# nRF52832.net
KiCad netlist of a schematic drawn in Altium Designer
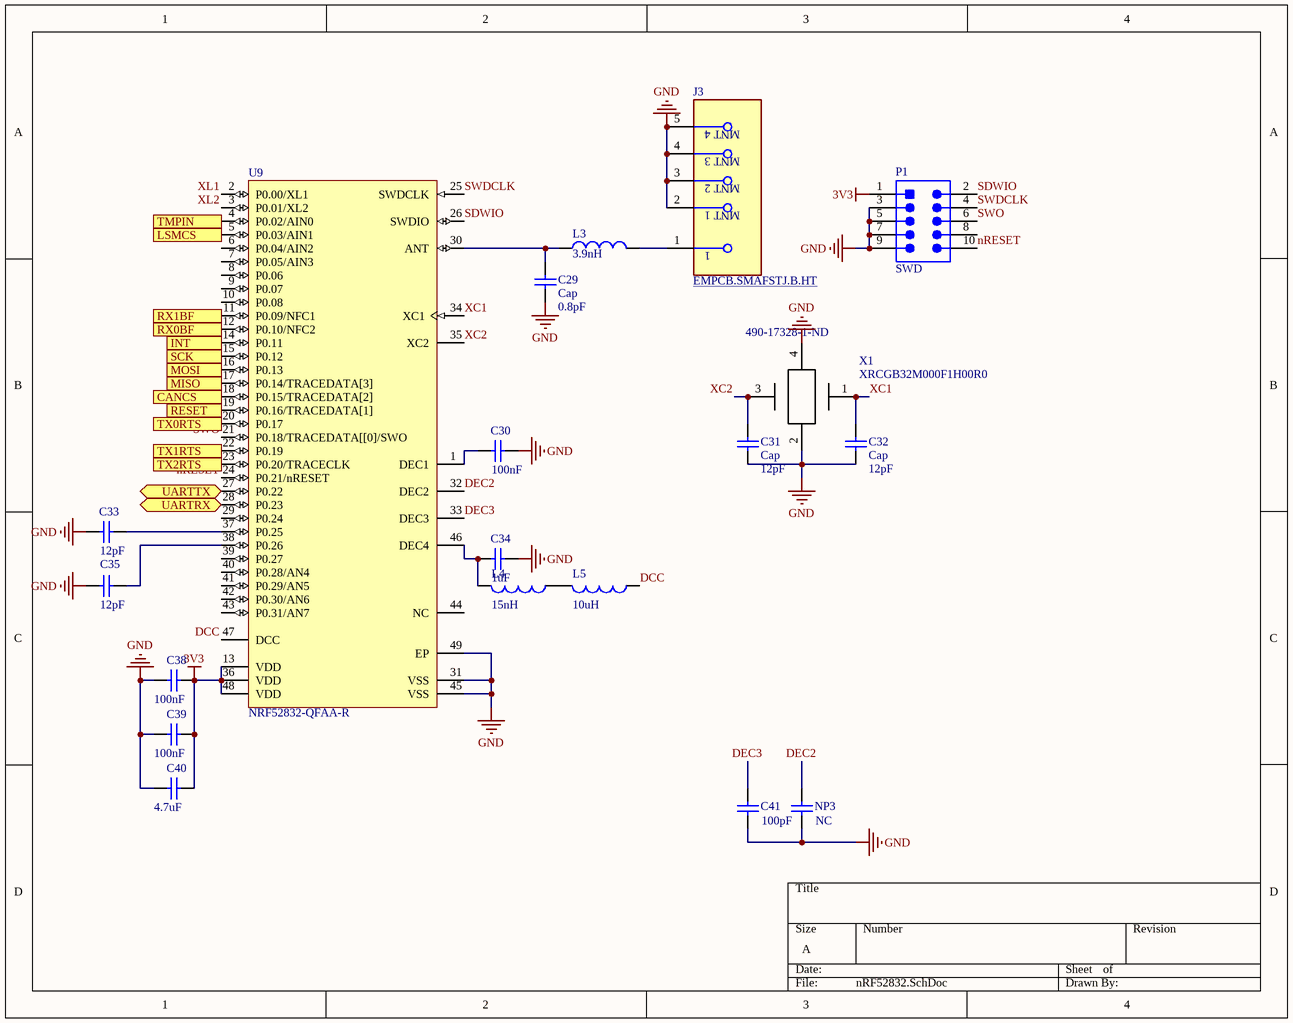
[diagram p0: nRF52832.SchDoc]

(export (version "E")
  (design (tool "Eeschema 10.0.6"))
  (components
    (comp (ref "C29")
      (value "Cap")
      (footprint "0402-A")
      (description "Capacitor")
      (fields (field (name "ALTIUM_VALUE") "0.8pF") (field (name "PUBLISHER") "Altium Limited"))
      (libsource (lib "Miscellaneous Devices") (part "Cap"))
    )
    (comp (ref "C30")
      (value "100nF")
      (footprint "0402-A")
      (description "Capacitor")
      (fields (field (name "Comment") "Cap") (field (name "PUBLISHER") "Altium Limited"))
      (libsource (lib "Miscellaneous Devices") (part "Cap"))
    )
    (comp (ref "C31")
      (value "Cap")
      (footprint "0402-A")
      (description "Capacitor")
      (fields (field (name "ALTIUM_VALUE") "12pF") (field (name "PUBLISHER") "Altium Limited"))
      (libsource (lib "Miscellaneous Devices") (part "Cap"))
    )
    (comp (ref "C32")
      (value "Cap")
      (footprint "0402-A")
      (description "Capacitor")
      (fields (field (name "ALTIUM_VALUE") "12pF") (field (name "PUBLISHER") "Altium Limited"))
      (libsource (lib "Miscellaneous Devices") (part "Cap"))
    )
    (comp (ref "C33")
      (value "12pF")
      (footprint "0402-A")
      (description "Capacitor")
      (fields (field (name "Comment") "Cap") (field (name "PUBLISHER") "Altium Limited"))
      (libsource (lib "Miscellaneous Devices") (part "Cap"))
    )
    (comp (ref "C34")
      (value "1uF")
      (footprint "1608[0603]")
      (description "Capacitor")
      (fields (field (name "Comment") "Cap") (field (name "PUBLISHER") "Altium Limited"))
      (libsource (lib "Miscellaneous Devices") (part "Cap"))
    )
    (comp (ref "C35")
      (value "12pF")
      (footprint "0402-A")
      (description "Capacitor")
      (fields (field (name "Comment") "Cap") (field (name "PUBLISHER") "Altium Limited"))
      (libsource (lib "Miscellaneous Devices") (part "Cap"))
    )
    (comp (ref "C38")
      (value "100nF")
      (footprint "0402-A")
      (description "Capacitor")
      (fields (field (name "Comment") "Cap") (field (name "PUBLISHER") "Altium Limited"))
      (libsource (lib "Miscellaneous Devices") (part "Cap"))
    )
    (comp (ref "C39")
      (value "100nF")
      (footprint "0402-A")
      (description "Capacitor")
      (fields (field (name "Comment") "Cap") (field (name "PUBLISHER") "Altium Limited"))
      (libsource (lib "Miscellaneous Devices") (part "Cap"))
    )
    (comp (ref "C40")
      (value "4.7uF")
      (footprint "6-0805_M")
      (description "Capacitor")
      (fields (field (name "Comment") "Cap") (field (name "PUBLISHER") "Altium Limited"))
      (libsource (lib "Miscellaneous Devices") (part "Cap"))
    )
    (comp (ref "C41")
      (value "100pF")
      (footprint "0402-A")
      (description "Capacitor")
      (fields (field (name "Comment") "Cap") (field (name "PUBLISHER") "Altium Limited"))
      (libsource (lib "Miscellaneous Devices") (part "Cap"))
    )
    (comp (ref "J3")
      (value "EMPCB.SMAFSTJ.B.HT")
      (footprint "FP-EMPCB_SMAFSTJ_B_HT-MFG")
      (description "CONN SMA JACK STR 50OHM EDGE MNT")
      (fields
        (field (name "OCTOPART") "https://octopart.com/empcb.smafstj.b.ht-taoglas-24204431")
        (field (name "MANUFACTURER") "Taoglas Limited")
      )
      (libsource (lib "Altium Content Vault") (part "c65b8a639cdaef1819ea20b5466f8fa"))
    )
    (comp (ref "L3")
      (value "3.9nH")
      (footprint "0402-A")
      (description "Inductor")
      (fields (field (name "PUBLISHER") "Altium Limited"))
      (libsource (lib "Miscellaneous Devices") (part "Inductor"))
    )
    (comp (ref "L4")
      (value "15nH")
      (footprint "0402-A")
      (description "Inductor")
      (fields (field (name "PUBLISHER") "Altium Limited"))
      (libsource (lib "Miscellaneous Devices") (part "Inductor"))
    )
    (comp (ref "L5")
      (value "10uH")
      (footprint "1608[0603]")
      (description "Inductor")
      (fields (field (name "PUBLISHER") "Altium Limited"))
      (libsource (lib "Miscellaneous Devices") (part "Inductor"))
    )
    (comp (ref "NP3")
      (value "NC")
      (footprint "0402-A")
      (description "Capacitor")
      (fields (field (name "Comment") "Cap") (field (name "PUBLISHER") "Altium Limited"))
      (libsource (lib "Miscellaneous Devices") (part "Cap"))
    )
    (comp (ref "P1")
      (value "SWD")
      (footprint "SMTC-FTSH-105-01-L-DV-K_V")
      (description "Male Header, Pitch 1.27 mm, 2 x 5 Position, Height 6.25 mm")
      (fields (field (name "MANUFACTURER") "Samtec"))
      (libsource (lib "Altium Content Vault") (part "CN-2P-M-R10"))
    )
    (comp (ref "U9")
      (value "NRF52832-QFAA-R")
      (footprint "NRSC-QF-48_M")
      (fields (field (name "MANUFACTURER") "Nordic Semiconductor"))
      (libsource (lib "Altium Content Vault") (part "NRSC-NRF52832-QF-48"))
    )
    (comp (ref "X1")
      (value "XRCGB32M000F1H00R0")
      (footprint "XRCGB32M000F1H00R0")
      (description "32MHz Crystal Oscillator")
      (fields (field (name "SUPPLIER PART NUMBER 1") "490-17328-1-ND"))
      (libsource (lib "XRCGB32M000F1H00R0") (part "XRCGB32M000F1H00R0"))
    )
  )
  (nets
    (net (code "1") (name "/CANCS") (class "Default")
      (node (ref "U9") (pin "18") (pinfunction "P0.15/TRACEDATA[2]_18") (pintype "bidirectional"))
    )
    (net (code "2") (name "/DCC") (class "Default")
      (node (ref "L5") (pin "1") (pinfunction "1_1") (pintype "passive"))
      (node (ref "U9") (pin "47") (pinfunction "DCC_47") (pintype "power_in"))
    )
    (net (code "3") (name "/DEC2") (class "Default")
      (node (ref "NP3") (pin "2") (pinfunction "2_2") (pintype "passive"))
      (node (ref "U9") (pin "32") (pinfunction "DEC2_32") (pintype "passive"))
    )
    (net (code "4") (name "/DEC3") (class "Default")
      (node (ref "C41") (pin "2") (pinfunction "2_2") (pintype "passive"))
      (node (ref "U9") (pin "33") (pinfunction "DEC3_33") (pintype "passive"))
    )
    (net (code "5") (name "/INT") (class "Default")
      (node (ref "U9") (pin "14") (pinfunction "P0.11_14") (pintype "bidirectional"))
    )
    (net (code "6") (name "/LSMCS") (class "Default")
      (node (ref "U9") (pin "5") (pinfunction "P0.03/AIN1_5") (pintype "bidirectional"))
    )
    (net (code "7") (name "/MISO") (class "Default")
      (node (ref "U9") (pin "17") (pinfunction "P0.14/TRACEDATA[3]_17") (pintype "bidirectional"))
    )
    (net (code "8") (name "/MOSI") (class "Default")
      (node (ref "U9") (pin "16") (pinfunction "P0.13_16") (pintype "bidirectional"))
    )
    (net (code "9") (name "/RESET") (class "Default")
      (node (ref "U9") (pin "19") (pinfunction "P0.16/TRACEDATA[1]_19") (pintype "bidirectional"))
    )
    (net (code "10") (name "/RX0BF") (class "Default")
      (node (ref "U9") (pin "12") (pinfunction "P0.10/NFC2_12") (pintype "bidirectional"))
    )
    (net (code "11") (name "/RX1BF") (class "Default")
      (node (ref "U9") (pin "11") (pinfunction "P0.09/NFC1_11") (pintype "bidirectional"))
    )
    (net (code "12") (name "/SCK") (class "Default")
      (node (ref "U9") (pin "15") (pinfunction "P0.12_15") (pintype "bidirectional"))
    )
    (net (code "13") (name "/SDWIO") (class "Default")
      (node (ref "P1") (pin "2") (pinfunction "2_2") (pintype "passive"))
      (node (ref "U9") (pin "26") (pinfunction "SWDIO_26") (pintype "bidirectional"))
    )
    (net (code "14") (name "/SWDCLK") (class "Default")
      (node (ref "P1") (pin "4") (pinfunction "4_4") (pintype "passive"))
      (node (ref "U9") (pin "25") (pinfunction "SWDCLK_25") (pintype "input"))
    )
    (net (code "15") (name "/SWO") (class "Default")
      (node (ref "P1") (pin "6") (pinfunction "6_6") (pintype "passive"))
      (node (ref "U9") (pin "21") (pinfunction "P0.18/TRACEDATA[[0]/SWO_21") (pintype "bidirectional"))
    )
    (net (code "16") (name "/TMPIN") (class "Default")
      (node (ref "U9") (pin "4") (pinfunction "P0.02/AIN0_4") (pintype "bidirectional"))
    )
    (net (code "17") (name "/TX0RTS") (class "Default")
      (node (ref "U9") (pin "20") (pinfunction "P0.17_20") (pintype "bidirectional"))
    )
    (net (code "18") (name "/TX1RTS") (class "Default")
      (node (ref "U9") (pin "22") (pinfunction "P0.19_22") (pintype "bidirectional"))
    )
    (net (code "19") (name "/TX2RTS") (class "Default")
      (node (ref "U9") (pin "23") (pinfunction "P0.20/TRACECLK_23") (pintype "bidirectional"))
    )
    (net (code "20") (name "/UARTRX") (class "Default")
      (node (ref "U9") (pin "28") (pinfunction "P0.23_28") (pintype "bidirectional"))
    )
    (net (code "21") (name "/UARTTX") (class "Default")
      (node (ref "U9") (pin "27") (pinfunction "P0.22_27") (pintype "bidirectional"))
    )
    (net (code "22") (name "/XC1") (class "Default")
      (node (ref "C32") (pin "2") (pinfunction "2_2") (pintype "passive"))
      (node (ref "U9") (pin "34") (pinfunction "XC1_34") (pintype "input"))
      (node (ref "X1") (pin "1") (pinfunction "1_1") (pintype "passive"))
    )
    (net (code "23") (name "/XC2") (class "Default")
      (node (ref "C31") (pin "2") (pinfunction "2_2") (pintype "passive"))
      (node (ref "U9") (pin "35") (pinfunction "XC2_35") (pintype "passive"))
      (node (ref "X1") (pin "3") (pintype "passive"))
    )
    (net (code "24") (name "/XL1") (class "Default")
      (node (ref "U9") (pin "2") (pinfunction "P0.00/XL1_2") (pintype "bidirectional"))
    )
    (net (code "25") (name "/XL2") (class "Default")
      (node (ref "U9") (pin "3") (pinfunction "P0.01/XL2_3") (pintype "bidirectional"))
    )
    (net (code "26") (name "/nRESET") (class "Default")
      (node (ref "P1") (pin "10") (pinfunction "10_10") (pintype "passive"))
      (node (ref "U9") (pin "24") (pinfunction "P0.21/nRESET_24") (pintype "bidirectional"))
    )
    (net (code "27") (name "3V3") (class "Default")
      (node (ref "C38") (pin "1") (pinfunction "1_1") (pintype "passive"))
      (node (ref "C39") (pin "1") (pinfunction "1_1") (pintype "passive"))
      (node (ref "C40") (pin "1") (pinfunction "1_1") (pintype "passive"))
      (node (ref "P1") (pin "1") (pinfunction "1_1") (pintype "passive"))
      (node (ref "U9") (pin "13") (pinfunction "VDD_13") (pintype "power_in"))
      (node (ref "U9") (pin "36") (pinfunction "VDD_36") (pintype "power_in"))
      (node (ref "U9") (pin "48") (pinfunction "VDD_48") (pintype "power_in"))
    )
    (net (code "28") (name "GND") (class "Default")
      (node (ref "C29") (pin "1") (pinfunction "1_1") (pintype "passive"))
      (node (ref "C30") (pin "1") (pinfunction "1_1") (pintype "passive"))
      (node (ref "C31") (pin "1") (pinfunction "1_1") (pintype "passive"))
      (node (ref "C32") (pin "1") (pinfunction "1_1") (pintype "passive"))
      (node (ref "C33") (pin "2") (pinfunction "2_2") (pintype "passive"))
      (node (ref "C34") (pin "1") (pinfunction "1_1") (pintype "passive"))
      (node (ref "C35") (pin "2") (pinfunction "2_2") (pintype "passive"))
      (node (ref "C38") (pin "2") (pinfunction "2_2") (pintype "passive"))
      (node (ref "C39") (pin "2") (pinfunction "2_2") (pintype "passive"))
      (node (ref "C40") (pin "2") (pinfunction "2_2") (pintype "passive"))
      (node (ref "C41") (pin "1") (pinfunction "1_1") (pintype "passive"))
      (node (ref "J3") (pin "2") (pinfunction "MNT_1_2") (pintype "passive"))
      (node (ref "J3") (pin "3") (pinfunction "MNT_2_3") (pintype "passive"))
      (node (ref "J3") (pin "4") (pinfunction "MNT_3_4") (pintype "passive"))
      (node (ref "J3") (pin "5") (pinfunction "MNT_4_5") (pintype "passive"))
      (node (ref "NP3") (pin "1") (pinfunction "1_1") (pintype "passive"))
      (node (ref "P1") (pin "3") (pinfunction "3_3") (pintype "passive"))
      (node (ref "P1") (pin "5") (pinfunction "5_5") (pintype "passive"))
      (node (ref "P1") (pin "7") (pinfunction "7_7") (pintype "passive"))
      (node (ref "P1") (pin "9") (pinfunction "9_9") (pintype "passive"))
      (node (ref "U9") (pin "31") (pinfunction "VSS_31") (pintype "power_in"))
      (node (ref "U9") (pin "45") (pinfunction "VSS_45") (pintype "power_in"))
      (node (ref "U9") (pin "49") (pinfunction "EP_49") (pintype "power_in"))
      (node (ref "X1") (pin "2") (pinfunction "3_2") (pintype "passive"))
      (node (ref "X1") (pin "4") (pinfunction "4_4") (pintype "passive"))
    )
    (net (code "29") (name "Net-(J3-Pad1)") (class "Default")
      (node (ref "J3") (pin "1") (pinfunction "1_1") (pintype "passive"))
      (node (ref "L3") (pin "2") (pinfunction "2_2") (pintype "passive"))
    )
    (net (code "30") (name "Net-(L4-Pad1)") (class "Default")
      (node (ref "L4") (pin "1") (pinfunction "1_1") (pintype "passive"))
      (node (ref "L5") (pin "2") (pinfunction "2_2") (pintype "passive"))
    )
    (net (code "31") (name "Net-(U9-ANT)") (class "Default")
      (node (ref "C29") (pin "2") (pinfunction "2_2") (pintype "passive"))
      (node (ref "L3") (pin "1") (pinfunction "1_1") (pintype "passive"))
      (node (ref "U9") (pin "30") (pinfunction "ANT_30") (pintype "bidirectional"))
    )
    (net (code "32") (name "Net-(U9-DEC1)") (class "Default")
      (node (ref "C30") (pin "2") (pinfunction "2_2") (pintype "passive"))
      (node (ref "U9") (pin "1") (pinfunction "DEC1_1") (pintype "passive"))
    )
    (net (code "33") (name "Net-(U9-DEC4)") (class "Default")
      (node (ref "C34") (pin "2") (pinfunction "2_2") (pintype "passive"))
      (node (ref "L4") (pin "2") (pinfunction "2_2") (pintype "passive"))
      (node (ref "U9") (pin "46") (pinfunction "DEC4_46") (pintype "passive"))
    )
    (net (code "34") (name "Net-(U9-P0.25)") (class "Default")
      (node (ref "C33") (pin "1") (pinfunction "1_1") (pintype "passive"))
      (node (ref "U9") (pin "37") (pinfunction "P0.25_37") (pintype "bidirectional"))
    )
    (net (code "35") (name "Net-(U9-P0.26)") (class "Default")
      (node (ref "C35") (pin "1") (pinfunction "1_1") (pintype "passive"))
      (node (ref "U9") (pin "38") (pinfunction "P0.26_38") (pintype "bidirectional"))
    )
    (net (code "36") (name "unconnected-(P1-Pad8)") (class "Default")
      (node (ref "P1") (pin "8") (pinfunction "8_8") (pintype "passive"))
    )
    (net (code "37") (name "unconnected-(U9-NC-Pad44)") (class "Default")
      (node (ref "U9") (pin "44") (pinfunction "NC_44") (pintype "passive"))
    )
    (net (code "38") (name "unconnected-(U9-P0.04{slash}AIN2-Pad6)") (class "Default")
      (node (ref "U9") (pin "6") (pinfunction "P0.04/AIN2_6") (pintype "bidirectional"))
    )
    (net (code "39") (name "unconnected-(U9-P0.05{slash}AIN3-Pad7)") (class "Default")
      (node (ref "U9") (pin "7") (pinfunction "P0.05/AIN3_7") (pintype "bidirectional"))
    )
    (net (code "40") (name "unconnected-(U9-P0.06-Pad8)") (class "Default")
      (node (ref "U9") (pin "8") (pinfunction "P0.06_8") (pintype "bidirectional"))
    )
    (net (code "41") (name "unconnected-(U9-P0.07-Pad9)") (class "Default")
      (node (ref "U9") (pin "9") (pinfunction "P0.07_9") (pintype "bidirectional"))
    )
    (net (code "42") (name "unconnected-(U9-P0.08-Pad10)") (class "Default")
      (node (ref "U9") (pin "10") (pinfunction "P0.08_10") (pintype "bidirectional"))
    )
    (net (code "43") (name "unconnected-(U9-P0.24-Pad29)") (class "Default")
      (node (ref "U9") (pin "29") (pinfunction "P0.24_29") (pintype "bidirectional"))
    )
    (net (code "44") (name "unconnected-(U9-P0.27-Pad39)") (class "Default")
      (node (ref "U9") (pin "39") (pinfunction "P0.27_39") (pintype "bidirectional"))
    )
    (net (code "45") (name "unconnected-(U9-P0.28{slash}AN4-Pad40)") (class "Default")
      (node (ref "U9") (pin "40") (pinfunction "P0.28/AN4_40") (pintype "bidirectional"))
    )
    (net (code "46") (name "unconnected-(U9-P0.29{slash}AN5-Pad41)") (class "Default")
      (node (ref "U9") (pin "41") (pinfunction "P0.29/AN5_41") (pintype "bidirectional"))
    )
    (net (code "47") (name "unconnected-(U9-P0.30{slash}AN6-Pad42)") (class "Default")
      (node (ref "U9") (pin "42") (pinfunction "P0.30/AN6_42") (pintype "bidirectional"))
    )
    (net (code "48") (name "unconnected-(U9-P0.31{slash}AN7-Pad43)") (class "Default")
      (node (ref "U9") (pin "43") (pinfunction "P0.31/AN7_43") (pintype "bidirectional"))
    )
  )
)
